# 08_Ethernet_USB.net
KiCad netlist of a schematic drawn in Altium Designer
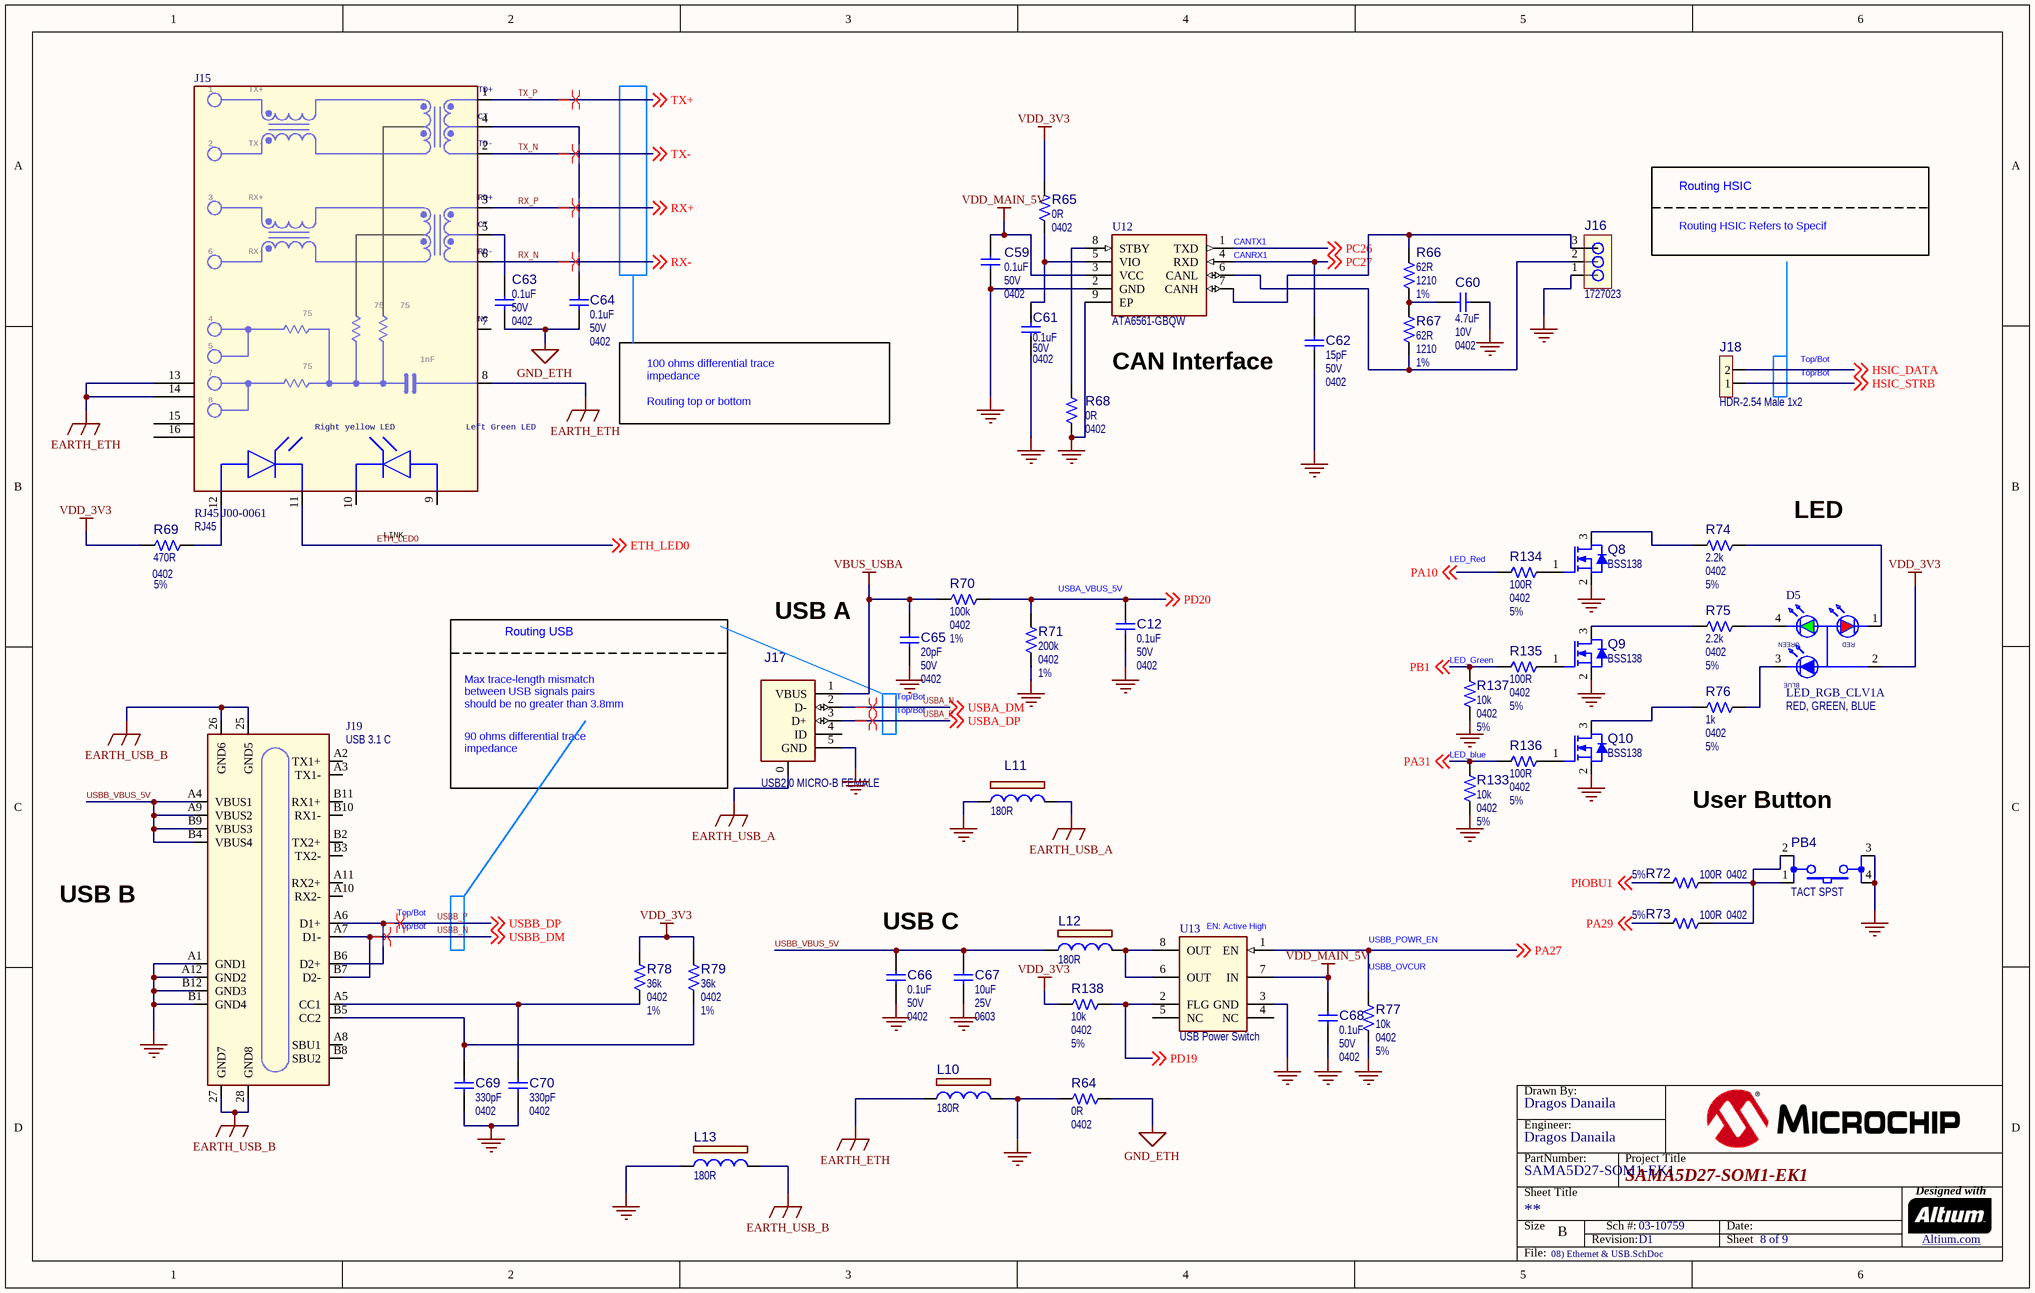
[diagram p0: 08) Ethernet & USB.SchDoc]

(export (version "E")
  (design (tool "Eeschema 10.0.6"))
  (components
    (comp (ref "C12")
      (value "0.1uF")
      (footprint "CAP_C_0402")
      (description "Capacitor")
      (fields
        (field (name "VOLTAGE") "50V")
        (field (name "PACKAGE") "0402")
        (field (name "TOLERANCE") "10%")
        (field (name "Comment") "Capacitor NP")
        (field (name "OWNER") "Jamus Griego")
      )
      (libsource (lib "MCHP-CDB") (part "Capacitor NP"))
    )
    (comp (ref "C59")
      (value "0.1uF")
      (footprint "CAP_C_0402")
      (description "Capacitor")
      (fields
        (field (name "VOLTAGE") "50V")
        (field (name "PACKAGE") "0402")
        (field (name "TOLERANCE") "10%")
        (field (name "Comment") "Capacitor NP")
        (field (name "OWNER") "Jamus Griego")
      )
      (libsource (lib "MCHP-CDB") (part "Capacitor NP"))
    )
    (comp (ref "C60")
      (value "4.7uF")
      (footprint "CAP_C_0402")
      (description "Capacitor")
      (fields
        (field (name "VOLTAGE") "10V")
        (field (name "PACKAGE") "0402")
        (field (name "TOLERANCE") "10%")
        (field (name "Comment") "Capacitor NP")
        (field (name "OWNER") "Jesus Aviles")
      )
      (libsource (lib "MCHP-CDB") (part "Capacitor NP"))
    )
    (comp (ref "C61")
      (value "0.1uF")
      (footprint "CAP_C_0402")
      (description "Capacitor")
      (fields
        (field (name "VOLTAGE") "50V")
        (field (name "PACKAGE") "0402")
        (field (name "TOLERANCE") "10%")
        (field (name "Comment") "Capacitor NP")
        (field (name "OWNER") "Jamus Griego")
      )
      (libsource (lib "MCHP-CDB") (part "Capacitor NP"))
    )
    (comp (ref "C62")
      (value "15pF")
      (footprint "CAP_C_0402")
      (description "Capacitor")
      (fields
        (field (name "VOLTAGE") "50V")
        (field (name "PACKAGE") "0402")
        (field (name "TOLERANCE") "5%")
        (field (name "Comment") "Capacitor NP")
      )
      (libsource (lib "MCHP-CDB") (part "Capacitor NP"))
    )
    (comp (ref "C63")
      (value "0.1uF")
      (footprint "CAP_C_0402")
      (description "Capacitor")
      (fields
        (field (name "VOLTAGE") "50V")
        (field (name "PACKAGE") "0402")
        (field (name "TOLERANCE") "10%")
        (field (name "Comment") "Capacitor NP")
        (field (name "OWNER") "Jamus Griego")
      )
      (libsource (lib "MCHP-CDB") (part "Capacitor NP"))
    )
    (comp (ref "C64")
      (value "0.1uF")
      (footprint "CAP_C_0402")
      (description "Capacitor")
      (fields
        (field (name "VOLTAGE") "50V")
        (field (name "PACKAGE") "0402")
        (field (name "TOLERANCE") "10%")
        (field (name "Comment") "Capacitor NP")
        (field (name "OWNER") "Jamus Griego")
      )
      (libsource (lib "MCHP-CDB") (part "Capacitor NP"))
    )
    (comp (ref "C65")
      (value "20pF")
      (footprint "CAP_C_0402")
      (description "Capacitor")
      (fields
        (field (name "VOLTAGE") "50V")
        (field (name "PACKAGE") "0402")
        (field (name "TOLERANCE") "5%")
        (field (name "Comment") "Capacitor NP")
      )
      (libsource (lib "MCHP-CDB") (part "Capacitor NP"))
    )
    (comp (ref "C66")
      (value "0.1uF")
      (footprint "CAP_C_0402")
      (description "Capacitor")
      (fields
        (field (name "VOLTAGE") "50V")
        (field (name "PACKAGE") "0402")
        (field (name "TOLERANCE") "10%")
        (field (name "Comment") "Capacitor NP")
        (field (name "OWNER") "Jamus Griego")
      )
      (libsource (lib "MCHP-CDB") (part "Capacitor NP"))
    )
    (comp (ref "C67")
      (value "10uF")
      (footprint "CAP_C_0603")
      (description "Capacitor")
      (fields
        (field (name "VOLTAGE") "25V")
        (field (name "PACKAGE") "0603")
        (field (name "TOLERANCE") "20%")
        (field (name "Comment") "Capacitor NP")
        (field (name "OWNER") "Razvan Cristescu")
      )
      (libsource (lib "MCHP-CDB") (part "Capacitor NP"))
    )
    (comp (ref "C68")
      (value "0.1uF")
      (footprint "CAP_C_0402")
      (description "Capacitor")
      (fields
        (field (name "VOLTAGE") "50V")
        (field (name "PACKAGE") "0402")
        (field (name "TOLERANCE") "10%")
        (field (name "Comment") "Capacitor NP")
        (field (name "OWNER") "Jamus Griego")
      )
      (libsource (lib "MCHP-CDB") (part "Capacitor NP"))
    )
    (comp (ref "C69")
      (value "330pF")
      (footprint "CAP_C_0402")
      (description "Capacitor")
      (fields
        (field (name "PACKAGE") "0402")
        (field (name "TOLERANCE") "5%")
        (field (name "Comment") "Capacitor NP")
        (field (name "OWNER") "Jamus Griego")
      )
      (libsource (lib "MCHP-CDB") (part "Capacitor NP"))
    )
    (comp (ref "C70")
      (value "330pF")
      (footprint "CAP_C_0402")
      (description "Capacitor")
      (fields
        (field (name "PACKAGE") "0402")
        (field (name "TOLERANCE") "5%")
        (field (name "Comment") "Capacitor NP")
        (field (name "OWNER") "Jamus Griego")
      )
      (libsource (lib "MCHP-CDB") (part "Capacitor NP"))
    )
    (comp (ref "D5")
      (value "LED_RGB_CLV1A")
      (footprint "PLCC-4_CLV1A-FKB")
      (fields
        (field (name "ALTIUM_VALUE") "RED, GREEN, BLUE")
        (field (name "POWER") "130mW, 100mW, 100mW")
        (field (name "OWNER") "Randolph Sobrepena")
      )
      (libsource (lib "MCHP-CDB") (part "LED_RGB_CLV1A"))
    )
    (comp (ref "J15")
      (value "RJ45 J00-0061")
      (footprint "J00-0061NL_RJ45_connector")
      (description "CON MODULAR RJ45 ETHERNET J00-0061NL")
      (fields (field (name "ALTIUM_VALUE") "RJ45") (field (name "OWNER") "Dragos Danaila"))
      (libsource (lib "MCHP-CDB") (part "RJ45 J00-0061"))
    )
    (comp (ref "J16")
      (value "1727023")
      (footprint "CON_TERMINAL_3.81_1x3_TH_RA_PHO_1727023")
      (fields
        (field (name "VOLTAGE") "300V")
        (field (name "Comment") "CON TERM BLK 1x3 TH Mount")
        (field (name "OWNER") "Dragos Danaila")
      )
      (libsource (lib "MCHP-CDB") (part "CON TERM BLK 1x3 TH Mount"))
    )
    (comp (ref "J17")
      (value "USB2.0 MICRO-B FEMALE")
      (footprint "CON_USB_Micro-AB_SMD_TH_RA_FCI_10118194-0001LF")
      (description "Connector USB Mini")
      (fields (field (name "Comment") "CON USB2.0 Mini_Micro") (field (name "OWNER") "Jamus Griego"))
      (libsource (lib "MCHP-CDB") (part "CON USB2.0 Mini_Micro"))
    )
    (comp (ref "J18")
      (value "HDR-2.54 Male 1x2")
      (footprint "HDR_M_2.54_1x2")
      (fields (field (name "Comment") "Header 1x2") (field (name "OWNER") "Bogdan P (M91398)"))
      (libsource (lib "MCHP-CDB") (part "Header 1x2"))
    )
    (comp (ref "J19")
      (value "USB 3.1 C")
      (footprint "CON USB3.1-C Female SMD RA 1054500101")
      (fields
        (field (name "VOLTAGE") "30V")
        (field (name "Comment") "CON USB3.1-C Female SMD RA")
        (field (name "OWNER") "Dragos Danaila")
      )
      (libsource (lib "MCHP-CDB") (part "CON USB3.1-C Female SMD RA"))
    )
    (comp (ref "L10")
      (value "180R")
      (footprint "IND_C_0603")
      (description "FERRITE 180R 1.5A SMD 0603")
      (fields (field (name "Comment") "Ferrite Bead") (field (name "OWNER") "Dragos Danaila"))
      (libsource (lib "MCHP-CDB") (part "Ferrite Bead"))
    )
    (comp (ref "L11")
      (value "180R")
      (footprint "IND_C_0603")
      (description "FERRITE 180R 1.5A SMD 0603")
      (fields (field (name "Comment") "Ferrite Bead") (field (name "OWNER") "Dragos Danaila"))
      (libsource (lib "MCHP-CDB") (part "Ferrite Bead"))
    )
    (comp (ref "L12")
      (value "180R")
      (footprint "IND_C_0603")
      (description "FERRITE 180R 1.5A SMD 0603")
      (fields (field (name "Comment") "Ferrite Bead") (field (name "OWNER") "Dragos Danaila"))
      (libsource (lib "MCHP-CDB") (part "Ferrite Bead"))
    )
    (comp (ref "L13")
      (value "180R")
      (footprint "IND_C_0603")
      (description "FERRITE 180R 1.5A SMD 0603")
      (fields (field (name "Comment") "Ferrite Bead") (field (name "OWNER") "Dragos Danaila"))
      (libsource (lib "MCHP-CDB") (part "Ferrite Bead"))
    )
    (comp (ref "PB4")
      (value "TACT SPST")
      (footprint "SW_SMD_6mmX6mm_TL3301")
      (description "Switch")
      (fields (field (name "VOLTAGE") "12V") (field (name "Comment") "Switch 4 Pin"))
      (libsource (lib "MCHP-CDB") (part "Switch 4 Pin"))
    )
    (comp (ref "Q8")
      (value "BSS138")
      (footprint "SOT-23-3")
      (description "Transistor MOS")
      (fields
        (field (name "POWER") "360mW")
        (field (name "VOLTAGE") "50V")
        (field (name "OWNER") "Razvan Cristescu")
      )
      (libsource (lib "MCHP-CDB") (part "Transistor MOS-N GSD"))
    )
    (comp (ref "Q9")
      (value "BSS138")
      (footprint "SOT-23-3")
      (description "Transistor MOS")
      (fields
        (field (name "POWER") "360mW")
        (field (name "VOLTAGE") "50V")
        (field (name "OWNER") "Razvan Cristescu")
      )
      (libsource (lib "MCHP-CDB") (part "Transistor MOS-N GSD"))
    )
    (comp (ref "Q10")
      (value "BSS138")
      (footprint "SOT-23-3")
      (description "Transistor MOS")
      (fields
        (field (name "POWER") "360mW")
        (field (name "VOLTAGE") "50V")
        (field (name "OWNER") "Razvan Cristescu")
      )
      (libsource (lib "MCHP-CDB") (part "Transistor MOS-N GSD"))
    )
    (comp (ref "R64")
      (value "0R")
      (footprint "RES_C_0402")
      (description "Resistor")
      (fields (field (name "PACKAGE") "0402") (field (name "POWER") "1/10W"))
      (libsource (lib "MCHP-CDB") (part "Resistor"))
    )
    (comp (ref "R65")
      (value "0R")
      (footprint "RES_C_0402")
      (description "Resistor")
      (fields (field (name "PACKAGE") "0402") (field (name "POWER") "1/10W"))
      (libsource (lib "MCHP-CDB") (part "Resistor"))
    )
    (comp (ref "R66")
      (value "62R")
      (footprint "RES_C_1210")
      (description "Resistor")
      (fields
        (field (name "PACKAGE") "1210")
        (field (name "TOLERANCE") "1%")
        (field (name "VOLTAGE") "200V")
        (field (name "POWER") "1/2W")
        (field (name "OWNER") "Dragos Danaila")
      )
      (libsource (lib "MCHP-CDB") (part "Resistor"))
    )
    (comp (ref "R67")
      (value "62R")
      (footprint "RES_C_1210")
      (description "Resistor")
      (fields
        (field (name "PACKAGE") "1210")
        (field (name "TOLERANCE") "1%")
        (field (name "VOLTAGE") "200V")
        (field (name "POWER") "1/2W")
        (field (name "OWNER") "Dragos Danaila")
      )
      (libsource (lib "MCHP-CDB") (part "Resistor"))
    )
    (comp (ref "R68")
      (value "0R")
      (footprint "RES_C_0402")
      (description "Resistor")
      (fields (field (name "PACKAGE") "0402") (field (name "POWER") "1/10W"))
      (libsource (lib "MCHP-CDB") (part "Resistor"))
    )
    (comp (ref "R69")
      (value "470R")
      (footprint "RES_C_0402")
      (description "Resistor")
      (fields
        (field (name "PACKAGE") "0402")
        (field (name "TOLERANCE") "5%")
        (field (name "VOLTAGE") "50V")
        (field (name "POWER") "1/16W")
        (field (name "OWNER") "Sompoch Loboonlert")
      )
      (libsource (lib "MCHP-CDB") (part "Resistor"))
    )
    (comp (ref "R70")
      (value "100k")
      (footprint "RES_C_0402")
      (description "Resistor")
      (fields
        (field (name "PACKAGE") "0402")
        (field (name "TOLERANCE") "1%")
        (field (name "VOLTAGE") "50V")
        (field (name "POWER") "1/10W")
        (field (name "OWNER") "Tad Ahlvers")
      )
      (libsource (lib "MCHP-CDB") (part "Resistor"))
    )
    (comp (ref "R71")
      (value "200k")
      (footprint "RES_C_0402")
      (description "Resistor")
      (fields
        (field (name "PACKAGE") "0402")
        (field (name "TOLERANCE") "1%")
        (field (name "VOLTAGE") "50V")
        (field (name "POWER") "1/10W")
        (field (name "OWNER") "Tad Ahlvers")
      )
      (libsource (lib "MCHP-CDB") (part "Resistor"))
    )
    (comp (ref "R72")
      (value "100R")
      (footprint "RES_C_0402")
      (description "Resistor")
      (fields
        (field (name "PACKAGE") "0402")
        (field (name "TOLERANCE") "5%")
        (field (name "VOLTAGE") "50V")
        (field (name "POWER") "1/16W")
        (field (name "OWNER") "Sompoch Loboonlert")
      )
      (libsource (lib "MCHP-CDB") (part "Resistor"))
    )
    (comp (ref "R73")
      (value "100R")
      (footprint "RES_C_0402")
      (description "Resistor")
      (fields
        (field (name "PACKAGE") "0402")
        (field (name "TOLERANCE") "5%")
        (field (name "VOLTAGE") "50V")
        (field (name "POWER") "1/16W")
        (field (name "OWNER") "Sompoch Loboonlert")
      )
      (libsource (lib "MCHP-CDB") (part "Resistor"))
    )
    (comp (ref "R74")
      (value "2.2k")
      (footprint "RES_C_0402")
      (description "Resistor")
      (fields
        (field (name "PACKAGE") "0402")
        (field (name "TOLERANCE") "5%")
        (field (name "VOLTAGE") "50V")
        (field (name "POWER") "1/16W")
        (field (name "OWNER") "Tad Ahlvers")
      )
      (libsource (lib "MCHP-CDB") (part "Resistor"))
    )
    (comp (ref "R75")
      (value "2.2k")
      (footprint "RES_C_0402")
      (description "Resistor")
      (fields
        (field (name "PACKAGE") "0402")
        (field (name "TOLERANCE") "5%")
        (field (name "VOLTAGE") "50V")
        (field (name "POWER") "1/16W")
        (field (name "OWNER") "Tad Ahlvers")
      )
      (libsource (lib "MCHP-CDB") (part "Resistor"))
    )
    (comp (ref "R76")
      (value "1k")
      (footprint "RES_C_0402")
      (description "Resistor")
      (fields
        (field (name "PACKAGE") "0402")
        (field (name "TOLERANCE") "5%")
        (field (name "VOLTAGE") "50V")
        (field (name "POWER") "1/16W")
        (field (name "OWNER") "Tad Ahlvers")
      )
      (libsource (lib "MCHP-CDB") (part "Resistor"))
    )
    (comp (ref "R77")
      (value "10k")
      (footprint "RES_C_0402")
      (description "Resistor")
      (fields
        (field (name "PACKAGE") "0402")
        (field (name "TOLERANCE") "5%")
        (field (name "VOLTAGE") "50V")
        (field (name "POWER") "1/16W")
      )
      (libsource (lib "MCHP-CDB") (part "Resistor"))
    )
    (comp (ref "R78")
      (value "36k")
      (footprint "RES_C_0402")
      (description "Resistor")
      (fields
        (field (name "PACKAGE") "0402")
        (field (name "TOLERANCE") "1%")
        (field (name "VOLTAGE") "50V")
        (field (name "POWER") "1/16W")
        (field (name "OWNER") "Dragos Danaila")
      )
      (libsource (lib "MCHP-CDB") (part "Resistor"))
    )
    (comp (ref "R79")
      (value "36k")
      (footprint "RES_C_0402")
      (description "Resistor")
      (fields
        (field (name "PACKAGE") "0402")
        (field (name "TOLERANCE") "1%")
        (field (name "VOLTAGE") "50V")
        (field (name "POWER") "1/16W")
        (field (name "OWNER") "Dragos Danaila")
      )
      (libsource (lib "MCHP-CDB") (part "Resistor"))
    )
    (comp (ref "R133")
      (value "10k")
      (footprint "RES_C_0402")
      (description "Resistor")
      (fields
        (field (name "PACKAGE") "0402")
        (field (name "TOLERANCE") "5%")
        (field (name "VOLTAGE") "50V")
        (field (name "POWER") "1/16W")
      )
      (libsource (lib "MCHP-CDB") (part "Resistor"))
    )
    (comp (ref "R134")
      (value "100R")
      (footprint "RES_C_0402")
      (description "Resistor")
      (fields
        (field (name "PACKAGE") "0402")
        (field (name "TOLERANCE") "5%")
        (field (name "VOLTAGE") "50V")
        (field (name "POWER") "1/16W")
        (field (name "OWNER") "Sompoch Loboonlert")
      )
      (libsource (lib "MCHP-CDB") (part "Resistor"))
    )
    (comp (ref "R135")
      (value "100R")
      (footprint "RES_C_0402")
      (description "Resistor")
      (fields
        (field (name "PACKAGE") "0402")
        (field (name "TOLERANCE") "5%")
        (field (name "VOLTAGE") "50V")
        (field (name "POWER") "1/16W")
        (field (name "OWNER") "Sompoch Loboonlert")
      )
      (libsource (lib "MCHP-CDB") (part "Resistor"))
    )
    (comp (ref "R136")
      (value "100R")
      (footprint "RES_C_0402")
      (description "Resistor")
      (fields
        (field (name "PACKAGE") "0402")
        (field (name "TOLERANCE") "5%")
        (field (name "VOLTAGE") "50V")
        (field (name "POWER") "1/16W")
        (field (name "OWNER") "Sompoch Loboonlert")
      )
      (libsource (lib "MCHP-CDB") (part "Resistor"))
    )
    (comp (ref "R137")
      (value "10k")
      (footprint "RES_C_0402")
      (description "Resistor")
      (fields
        (field (name "PACKAGE") "0402")
        (field (name "TOLERANCE") "5%")
        (field (name "VOLTAGE") "50V")
        (field (name "POWER") "1/16W")
      )
      (libsource (lib "MCHP-CDB") (part "Resistor"))
    )
    (comp (ref "R138")
      (value "10k")
      (footprint "RES_C_0402")
      (description "Resistor")
      (fields
        (field (name "PACKAGE") "0402")
        (field (name "TOLERANCE") "5%")
        (field (name "VOLTAGE") "50V")
        (field (name "POWER") "1/16W")
      )
      (libsource (lib "MCHP-CDB") (part "Resistor"))
    )
    (comp (ref "U12")
      (value "ATA6561-GBQW")
      (footprint "DFN-8_3x3_EP2.4X1.55")
      (description "MCHP INTERFACE CAN ATA6561-GBQW VDFN-8")
      (fields (field (name "Comment") "ATA6561 VDFN-8") (field (name "OWNER") "Alexandru Chiser - M19201"))
      (libsource (lib "MCHP-CDB") (part "ATA6561 VDFN-8"))
    )
    (comp (ref "U13")
      (value "USB Power Switch")
      (footprint "SOIC-8")
      (fields
        (field (name "Comment") "MCHP ANALOG POWER SWITCH 5.5V 0.7A MIC2025-1YM SOIC8")
        (field (name "OWNER") "Dragos Danaila")
      )
      (libsource (lib "MCHP-CDB") (part "MCHP ANALOG POWER SWITCH 5.5V 0.7A MIC2025-1YM SOIC8"))
    )
  )
  (nets
    (net (code "1") (name "/USBB_VBUS_5V") (class "Default")
      (node (ref "C66") (pin "1") (pinfunction "1_1") (pintype "passive"))
      (node (ref "C67") (pin "1") (pinfunction "1_1") (pintype "passive"))
      (node (ref "J19") (pin "A4") (pinfunction "VBUS1_A4") (pintype "passive"))
      (node (ref "J19") (pin "A9") (pinfunction "VBUS2_A9") (pintype "passive"))
      (node (ref "J19") (pin "B4") (pinfunction "VBUS4_B4") (pintype "passive"))
      (node (ref "J19") (pin "B9") (pinfunction "VBUS3_B9") (pintype "passive"))
      (node (ref "L12") (pin "1") (pinfunction "1_1") (pintype "passive"))
    )
    (net (code "2") (name "EARTH_ETH") (class "Default")
      (node (ref "J15") (pin "13") (pinfunction "P13_13") (pintype "passive"))
      (node (ref "J15") (pin "14") (pinfunction "P14_14") (pintype "passive"))
      (node (ref "J15") (pin "8") (pinfunction "P8_8") (pintype "passive"))
      (node (ref "L10") (pin "1") (pinfunction "1_1") (pintype "passive"))
    )
    (net (code "3") (name "EARTH_USB_A") (class "Default")
      (node (ref "J17") (pin "0") (pinfunction "SHLD_0") (pintype "passive"))
      (node (ref "L11") (pin "2") (pinfunction "2_2") (pintype "passive"))
    )
    (net (code "4") (name "EARTH_USB_B") (class "Default")
      (node (ref "J19") (pin "25") (pinfunction "GND5_25") (pintype "passive"))
      (node (ref "J19") (pin "26") (pinfunction "GND6_26") (pintype "passive"))
      (node (ref "J19") (pin "27") (pinfunction "GND7_27") (pintype "passive"))
      (node (ref "J19") (pin "28") (pinfunction "GND8_28") (pintype "passive"))
      (node (ref "L13") (pin "2") (pinfunction "2_2") (pintype "passive"))
    )
    (net (code "5") (name "ETH_LED0") (class "Default")
      (node (ref "J15") (pin "11") (pinfunction "P11_11") (pintype "passive"))
    )
    (net (code "6") (name "GND_ETH") (class "Default")
      (node (ref "C63") (pin "2") (pinfunction "2_2") (pintype "passive"))
      (node (ref "C64") (pin "2") (pinfunction "2_2") (pintype "passive"))
      (node (ref "R64") (pin "2") (pinfunction "2_2") (pintype "passive"))
    )
    (net (code "7") (name "GND_POWER") (class "Default")
      (node (ref "C12") (pin "2") (pinfunction "2_2") (pintype "passive"))
      (node (ref "C59") (pin "2") (pinfunction "2_2") (pintype "passive"))
      (node (ref "C60") (pin "2") (pinfunction "2_2") (pintype "passive"))
      (node (ref "C61") (pin "2") (pinfunction "2_2") (pintype "passive"))
      (node (ref "C62") (pin "2") (pinfunction "2_2") (pintype "passive"))
      (node (ref "C65") (pin "2") (pinfunction "2_2") (pintype "passive"))
      (node (ref "C66") (pin "2") (pinfunction "2_2") (pintype "passive"))
      (node (ref "C67") (pin "2") (pinfunction "2_2") (pintype "passive"))
      (node (ref "C68") (pin "2") (pinfunction "2_2") (pintype "passive"))
      (node (ref "C69") (pin "2") (pinfunction "2_2") (pintype "passive"))
      (node (ref "C70") (pin "2") (pinfunction "2_2") (pintype "passive"))
      (node (ref "J16") (pin "1") (pinfunction "1_1") (pintype "passive"))
      (node (ref "J17") (pin "5") (pinfunction "GND_5") (pintype "power_in"))
      (node (ref "J19") (pin "A1") (pinfunction "GND1_A1") (pintype "passive"))
      (node (ref "J19") (pin "A12") (pinfunction "GND2_A12") (pintype "passive"))
      (node (ref "J19") (pin "B1") (pinfunction "GND4_B1") (pintype "passive"))
      (node (ref "J19") (pin "B12") (pinfunction "GND3_B12") (pintype "passive"))
      (node (ref "L10") (pin "2") (pinfunction "2_2") (pintype "passive"))
      (node (ref "L11") (pin "1") (pinfunction "1_1") (pintype "passive"))
      (node (ref "L13") (pin "1") (pinfunction "1_1") (pintype "passive"))
      (node (ref "PB4") (pin "3") (pinfunction "3_3") (pintype "passive"))
      (node (ref "PB4") (pin "4") (pinfunction "4_4") (pintype "passive"))
      (node (ref "Q10") (pin "2") (pinfunction "S_2") (pintype "passive"))
      (node (ref "Q8") (pin "2") (pinfunction "S_2") (pintype "passive"))
      (node (ref "Q9") (pin "2") (pinfunction "S_2") (pintype "passive"))
      (node (ref "R133") (pin "2") (pinfunction "2_2") (pintype "passive"))
      (node (ref "R137") (pin "2") (pinfunction "2_2") (pintype "passive"))
      (node (ref "R64") (pin "1") (pinfunction "1_1") (pintype "passive"))
      (node (ref "R68") (pin "2") (pinfunction "2_2") (pintype "passive"))
      (node (ref "R71") (pin "2") (pinfunction "2_2") (pintype "passive"))
      (node (ref "R77") (pin "2") (pinfunction "2_2") (pintype "passive"))
      (node (ref "U12") (pin "2") (pinfunction "GND_2") (pintype "power_in"))
      (node (ref "U12") (pin "9") (pinfunction "EP_9") (pintype "passive"))
      (node (ref "U13") (pin "3") (pinfunction "GND_3") (pintype "power_in"))
    )
    (net (code "8") (name "HSIC_DATA") (class "Default")
      (node (ref "J18") (pin "2") (pinfunction "2_2") (pintype "passive"))
    )
    (net (code "9") (name "HSIC_STRB") (class "Default")
      (node (ref "J18") (pin "1") (pinfunction "1_1") (pintype "passive"))
    )
    (net (code "10") (name "Net-(C60-Pad1)") (class "Default")
      (node (ref "C60") (pin "1") (pinfunction "1_1") (pintype "passive"))
      (node (ref "R66") (pin "2") (pinfunction "2_2") (pintype "passive"))
      (node (ref "R67") (pin "1") (pinfunction "1_1") (pintype "passive"))
    )
    (net (code "11") (name "Net-(D5-K1)") (class "Default")
      (node (ref "D5") (pin "1") (pinfunction "K1_1") (pintype "passive"))
      (node (ref "R74") (pin "2") (pinfunction "2_2") (pintype "passive"))
    )
    (net (code "12") (name "Net-(D5-K2)") (class "Default")
      (node (ref "D5") (pin "4") (pinfunction "K2_4") (pintype "passive"))
      (node (ref "R75") (pin "2") (pinfunction "2_2") (pintype "passive"))
    )
    (net (code "13") (name "Net-(D5-K3)") (class "Default")
      (node (ref "D5") (pin "3") (pinfunction "K3_3") (pintype "passive"))
      (node (ref "R76") (pin "2") (pinfunction "2_2") (pintype "passive"))
    )
    (net (code "14") (name "Net-(J15-P4)") (class "Default")
      (node (ref "C64") (pin "1") (pinfunction "1_1") (pintype "passive"))
      (node (ref "J15") (pin "4") (pinfunction "P4_4") (pintype "passive"))
    )
    (net (code "15") (name "Net-(J15-P5)") (class "Default")
      (node (ref "C63") (pin "1") (pinfunction "1_1") (pintype "passive"))
      (node (ref "J15") (pin "5") (pinfunction "P5_5") (pintype "passive"))
    )
    (net (code "16") (name "Net-(J15-P12)") (class "Default")
      (node (ref "J15") (pin "12") (pinfunction "P12_12") (pintype "passive"))
      (node (ref "R69") (pin "2") (pinfunction "2_2") (pintype "passive"))
    )
    (net (code "17") (name "Net-(J19-CC1)") (class "Default")
      (node (ref "C70") (pin "1") (pinfunction "1_1") (pintype "passive"))
      (node (ref "J19") (pin "A5") (pinfunction "CC1_A5") (pintype "passive"))
      (node (ref "R78") (pin "2") (pinfunction "2_2") (pintype "passive"))
    )
    (net (code "18") (name "Net-(J19-CC2)") (class "Default")
      (node (ref "C69") (pin "1") (pinfunction "1_1") (pintype "passive"))
      (node (ref "J19") (pin "B5") (pinfunction "CC2_B5") (pintype "passive"))
      (node (ref "R79") (pin "2") (pinfunction "2_2") (pintype "passive"))
    )
    (net (code "19") (name "Net-(L12-Pad2)") (class "Default")
      (node (ref "L12") (pin "2") (pinfunction "2_2") (pintype "passive"))
      (node (ref "U13") (pin "6") (pinfunction "OUT_6") (pintype "passive"))
      (node (ref "U13") (pin "8") (pinfunction "OUT_8") (pintype "power_in"))
    )
    (net (code "20") (name "Net-(PB4-Pad1)") (class "Default")
      (node (ref "PB4") (pin "1") (pinfunction "1_1") (pintype "passive"))
      (node (ref "PB4") (pin "2") (pinfunction "2_2") (pintype "passive"))
      (node (ref "R72") (pin "2") (pinfunction "2_2") (pintype "passive"))
      (node (ref "R73") (pin "2") (pinfunction "2_2") (pintype "passive"))
    )
    (net (code "21") (name "Net-(Q8-D)") (class "Default")
      (node (ref "Q8") (pin "3") (pinfunction "D_3") (pintype "passive"))
      (node (ref "R74") (pin "1") (pinfunction "1_1") (pintype "passive"))
    )
    (net (code "22") (name "Net-(Q8-G)") (class "Default")
      (node (ref "Q8") (pin "1") (pinfunction "G_1") (pintype "passive"))
      (node (ref "R134") (pin "2") (pinfunction "2_2") (pintype "passive"))
    )
    (net (code "23") (name "Net-(Q9-D)") (class "Default")
      (node (ref "Q9") (pin "3") (pinfunction "D_3") (pintype "passive"))
      (node (ref "R75") (pin "1") (pinfunction "1_1") (pintype "passive"))
    )
    (net (code "24") (name "Net-(Q9-G)") (class "Default")
      (node (ref "Q9") (pin "1") (pinfunction "G_1") (pintype "passive"))
      (node (ref "R135") (pin "2") (pinfunction "2_2") (pintype "passive"))
    )
    (net (code "25") (name "Net-(Q10-D)") (class "Default")
      (node (ref "Q10") (pin "3") (pinfunction "D_3") (pintype "passive"))
      (node (ref "R76") (pin "1") (pinfunction "1_1") (pintype "passive"))
    )
    (net (code "26") (name "Net-(Q10-G)") (class "Default")
      (node (ref "Q10") (pin "1") (pinfunction "G_1") (pintype "passive"))
      (node (ref "R136") (pin "2") (pinfunction "2_2") (pintype "passive"))
    )
    (net (code "27") (name "Net-(U12-CANH)") (class "Default")
      (node (ref "J16") (pin "3") (pinfunction "3_3") (pintype "passive"))
      (node (ref "R66") (pin "1") (pinfunction "1_1") (pintype "passive"))
      (node (ref "U12") (pin "7") (pinfunction "CANH_7") (pintype "bidirectional"))
    )
    (net (code "28") (name "Net-(U12-CANL)") (class "Default")
      (node (ref "J16") (pin "2") (pinfunction "2_2") (pintype "passive"))
      (node (ref "R67") (pin "2") (pinfunction "2_2") (pintype "passive"))
      (node (ref "U12") (pin "6") (pinfunction "CANL_6") (pintype "bidirectional"))
    )
    (net (code "29") (name "Net-(U12-STBY)") (class "Default")
      (node (ref "R68") (pin "1") (pinfunction "1_1") (pintype "passive"))
      (node (ref "U12") (pin "8") (pinfunction "STBY_8") (pintype "input"))
    )
    (net (code "30") (name "Net-(U12-VIO)") (class "Default")
      (node (ref "C61") (pin "1") (pinfunction "1_1") (pintype "passive"))
      (node (ref "R65") (pin "2") (pinfunction "2_2") (pintype "passive"))
      (node (ref "U12") (pin "5") (pinfunction "VIO_5") (pintype "power_in"))
    )
    (net (code "31") (name "PA10") (class "Default")
      (node (ref "R134") (pin "1") (pinfunction "1_1") (pintype "passive"))
    )
    (net (code "32") (name "PA27") (class "Default")
      (node (ref "R77") (pin "1") (pinfunction "1_1") (pintype "passive"))
      (node (ref "U13") (pin "1") (pinfunction "EN_1") (pintype "input"))
    )
    (net (code "33") (name "PA29") (class "Default")
      (node (ref "R73") (pin "1") (pinfunction "1_1") (pintype "passive"))
    )
    (net (code "34") (name "PA31") (class "Default")
      (node (ref "R133") (pin "1") (pinfunction "1_1") (pintype "passive"))
      (node (ref "R136") (pin "1") (pinfunction "1_1") (pintype "passive"))
    )
    (net (code "35") (name "PB1") (class "Default")
      (node (ref "R135") (pin "1") (pinfunction "1_1") (pintype "passive"))
      (node (ref "R137") (pin "1") (pinfunction "1_1") (pintype "passive"))
    )
    (net (code "36") (name "PC26") (class "Default")
      (node (ref "U12") (pin "1") (pinfunction "TXD_1") (pintype "output"))
    )
    (net (code "37") (name "PC27") (class "Default")
      (node (ref "C62") (pin "1") (pinfunction "1_1") (pintype "passive"))
      (node (ref "U12") (pin "4") (pinfunction "RXD_4") (pintype "input"))
    )
    (net (code "38") (name "PD19") (class "Default")
      (node (ref "R138") (pin "2") (pinfunction "2_2") (pintype "passive"))
      (node (ref "U13") (pin "2") (pinfunction "FLG_2") (pintype "open_collector"))
    )
    (net (code "39") (name "PD20") (class "Default")
      (node (ref "C12") (pin "1") (pinfunction "1_1") (pintype "passive"))
      (node (ref "R70") (pin "2") (pinfunction "2_2") (pintype "passive"))
      (node (ref "R71") (pin "1") (pinfunction "1_1") (pintype "passive"))
    )
    (net (code "40") (name "PIOBU1") (class "Default")
      (node (ref "R72") (pin "1") (pinfunction "1_1") (pintype "passive"))
    )
    (net (code "41") (name "RX+") (class "Default")
      (node (ref "J15") (pin "3") (pinfunction "P3_3") (pintype "passive"))
    )
    (net (code "42") (name "RX-") (class "Default")
      (node (ref "J15") (pin "6") (pinfunction "P6_6") (pintype "passive"))
    )
    (net (code "43") (name "TX+") (class "Default")
      (node (ref "J15") (pin "1") (pinfunction "P1_1") (pintype "passive"))
    )
    (net (code "44") (name "TX-") (class "Default")
      (node (ref "J15") (pin "2") (pinfunction "P2_2") (pintype "passive"))
    )
    (net (code "45") (name "USBA_DM") (class "Default")
      (node (ref "J17") (pin "2") (pinfunction "D-_2") (pintype "bidirectional"))
    )
    (net (code "46") (name "USBA_DP") (class "Default")
      (node (ref "J17") (pin "3") (pinfunction "D+_3") (pintype "bidirectional"))
    )
    (net (code "47") (name "USBB_DM") (class "Default")
      (node (ref "J19") (pin "A7") (pinfunction "D1-_A7") (pintype "passive"))
      (node (ref "J19") (pin "B7") (pinfunction "D2-_B7") (pintype "passive"))
    )
    (net (code "48") (name "USBB_DP") (class "Default")
      (node (ref "J19") (pin "A6") (pinfunction "D1+_A6") (pintype "passive"))
      (node (ref "J19") (pin "B6") (pinfunction "D2+_B6") (pintype "passive"))
    )
    (net (code "49") (name "VBUS_USBA") (class "Default")
      (node (ref "C65") (pin "1") (pinfunction "1_1") (pintype "passive"))
      (node (ref "J17") (pin "1") (pinfunction "VBUS_1") (pintype "power_in"))
      (node (ref "R70") (pin "1") (pinfunction "1_1") (pintype "passive"))
    )
    (net (code "50") (name "VDD_3V3") (class "Default")
      (node (ref "D5") (pin "2") (pinfunction "A_2") (pintype "passive"))
      (node (ref "R138") (pin "1") (pinfunction "1_1") (pintype "passive"))
      (node (ref "R65") (pin "1") (pinfunction "1_1") (pintype "passive"))
      (node (ref "R69") (pin "1") (pinfunction "1_1") (pintype "passive"))
      (node (ref "R78") (pin "1") (pinfunction "1_1") (pintype "passive"))
      (node (ref "R79") (pin "1") (pinfunction "1_1") (pintype "passive"))
    )
    (net (code "51") (name "VDD_MAIN_5V") (class "Default")
      (node (ref "C59") (pin "1") (pinfunction "1_1") (pintype "passive"))
      (node (ref "C68") (pin "1") (pinfunction "1_1") (pintype "passive"))
      (node (ref "U12") (pin "3") (pinfunction "VCC_3") (pintype "power_in"))
      (node (ref "U13") (pin "7") (pinfunction "IN_7") (pintype "power_in"))
    )
    (net (code "52") (name "unconnected-(J15-P7-Pad7)") (class "Default")
      (node (ref "J15") (pin "7") (pinfunction "P7_7") (pintype "passive"))
    )
    (net (code "53") (name "unconnected-(J15-P9-Pad9)") (class "Default")
      (node (ref "J15") (pin "9") (pinfunction "P9_9") (pintype "passive"))
    )
    (net (code "54") (name "unconnected-(J15-P10-Pad10)") (class "Default")
      (node (ref "J15") (pin "10") (pinfunction "P10_10") (pintype "passive"))
    )
    (net (code "55") (name "unconnected-(J15-P15-Pad15)") (class "Default")
      (node (ref "J15") (pin "15") (pinfunction "P15_15") (pintype "passive"))
    )
    (net (code "56") (name "unconnected-(J15-P16-Pad16)") (class "Default")
      (node (ref "J15") (pin "16") (pinfunction "P16_16") (pintype "passive"))
    )
    (net (code "57") (name "unconnected-(J17-ID-Pad4)") (class "Default")
      (node (ref "J17") (pin "4") (pinfunction "ID_4") (pintype "passive"))
    )
    (net (code "58") (name "unconnected-(J19-RX1+-PadB11)") (class "Default")
      (node (ref "J19") (pin "B11") (pinfunction "RX1+_B11") (pintype "passive"))
    )
    (net (code "59") (name "unconnected-(J19-RX1--PadB10)") (class "Default")
      (node (ref "J19") (pin "B10") (pinfunction "RX1-_B10") (pintype "passive"))
    )
    (net (code "60") (name "unconnected-(J19-RX2+-PadA11)") (class "Default")
      (node (ref "J19") (pin "A11") (pinfunction "RX2+_A11") (pintype "passive"))
    )
    (net (code "61") (name "unconnected-(J19-RX2--PadA10)") (class "Default")
      (node (ref "J19") (pin "A10") (pinfunction "RX2-_A10") (pintype "passive"))
    )
    (net (code "62") (name "unconnected-(J19-SBU1-PadA8)") (class "Default")
      (node (ref "J19") (pin "A8") (pinfunction "SBU1_A8") (pintype "passive"))
    )
    (net (code "63") (name "unconnected-(J19-SBU2-PadB8)") (class "Default")
      (node (ref "J19") (pin "B8") (pinfunction "SBU2_B8") (pintype "passive"))
    )
    (net (code "64") (name "unconnected-(J19-TX1+-PadA2)") (class "Default")
      (node (ref "J19") (pin "A2") (pinfunction "TX1+_A2") (pintype "passive"))
    )
    (net (code "65") (name "unconnected-(J19-TX1--PadA3)") (class "Default")
      (node (ref "J19") (pin "A3") (pinfunction "TX1-_A3") (pintype "passive"))
    )
    (net (code "66") (name "unconnected-(J19-TX2+-PadB2)") (class "Default")
      (node (ref "J19") (pin "B2") (pinfunction "TX2+_B2") (pintype "passive"))
    )
    (net (code "67") (name "unconnected-(J19-TX2--PadB3)") (class "Default")
      (node (ref "J19") (pin "B3") (pinfunction "TX2-_B3") (pintype "passive"))
    )
    (net (code "68") (name "unconnected-(U13-NC-Pad4)") (class "Default")
      (node (ref "U13") (pin "4") (pinfunction "NC_4") (pintype "passive"))
    )
    (net (code "69") (name "unconnected-(U13-NC-Pad5)") (class "Default")
      (node (ref "U13") (pin "5") (pinfunction "NC_5") (pintype "passive"))
    )
  )
)
